# CLOCK_GENERATOR.net
KiCad netlist of a schematic drawn in Altium Designer
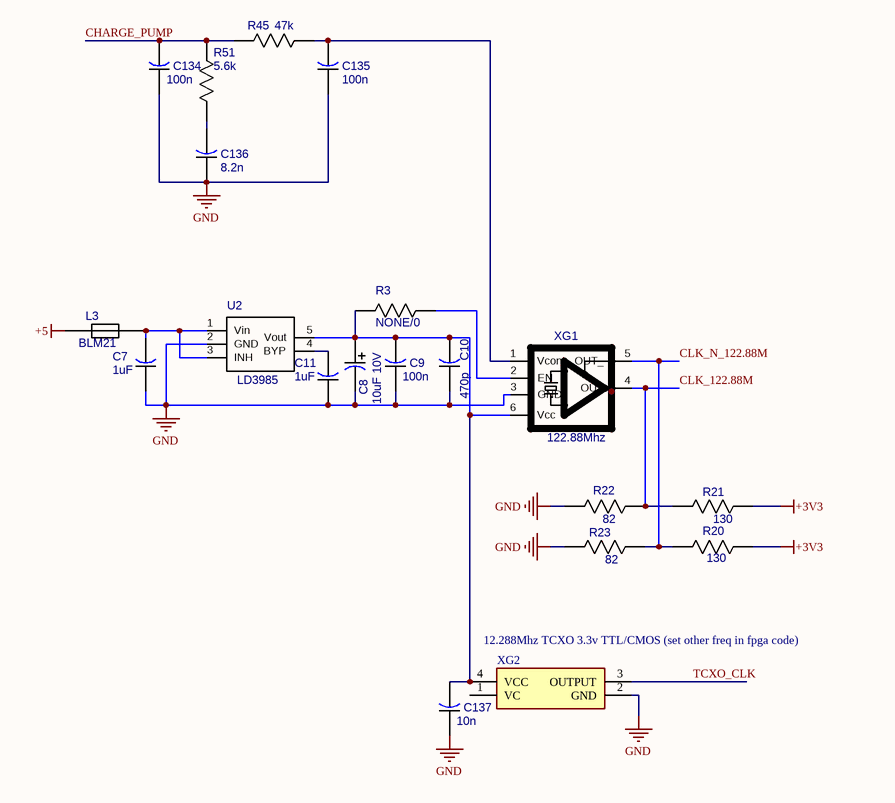
[diagram p0: CLOCK_GENERATOR.SchDoc]

(export (version "E")
  (design (tool "Eeschema 10.0.6"))
  (components
    (comp (ref "C7")
      (value "1uF")
      (footprint "CAP_0805")
      (description "CAP_0805")
      (libsource (lib "*") (part "CAP_0805"))
    )
    (comp (ref "C8")
      (value "10uF 10V")
      (footprint "CAPAE_4.3x4.3h5.4")
      (description "CAPAE_4.3x4.3h5.4")
      (libsource (lib "*") (part "CAPAE_4.3x4.3h5.4"))
    )
    (comp (ref "C9")
      (value "100n")
      (footprint "CAP_0805")
      (description "CAP_0805")
      (libsource (lib "*") (part "CAP_0805"))
    )
    (comp (ref "C10")
      (value "470p")
      (footprint "CAP_0805")
      (description "CAP_0805")
      (libsource (lib "*") (part "CAP_0805"))
    )
    (comp (ref "C11")
      (value "1uF")
      (footprint "CAP_0805")
      (description "CAP_0805")
      (libsource (lib "*") (part "CAP_0805"))
    )
    (comp (ref "C134")
      (value "100n")
      (footprint "CAP_0805")
      (description "CAP_0805")
      (libsource (lib "*") (part "CAP_0805"))
    )
    (comp (ref "C135")
      (value "100n")
      (footprint "CAP_0805")
      (description "CAP_0805")
      (libsource (lib "*") (part "CAP_0805"))
    )
    (comp (ref "C136")
      (value "8.2n")
      (footprint "CAP_0805")
      (description "CAP_0805")
      (libsource (lib "*") (part "CAP_0805"))
    )
    (comp (ref "C137")
      (value "10n")
      (footprint "CAP_0805")
      (description "CAP_0805")
      (libsource (lib "*") (part "CAP_0805"))
    )
    (comp (ref "L3")
      (value "BLM21")
      (footprint "CAP_0805")
      (libsource (lib "MOTHERBOARD_1") (part "IND_FERRITE_BEAD"))
    )
    (comp (ref "R3")
      (value "NONE/0")
      (footprint "RES_0805")
      (description "By used crystal")
      (fields (field (name "Comment") "0/NONE"))
      (libsource (lib "*") (part "RES_0805"))
    )
    (comp (ref "R20")
      (value "130")
      (footprint "RES_0805")
      (description "RES_0805")
      (libsource (lib "*") (part "RES_0805"))
    )
    (comp (ref "R21")
      (value "130")
      (footprint "RES_0805")
      (description "RES_0805")
      (libsource (lib "*") (part "RES_0805"))
    )
    (comp (ref "R22")
      (value "82")
      (footprint "RES_0805")
      (description "RES_0805")
      (libsource (lib "*") (part "RES_0805"))
    )
    (comp (ref "R23")
      (value "82")
      (footprint "RES_0805")
      (description "RES_0805")
      (libsource (lib "*") (part "RES_0805"))
    )
    (comp (ref "R45")
      (value "47k")
      (footprint "RES_0805")
      (description "RES_0805")
      (libsource (lib "*") (part "RES_0805"))
    )
    (comp (ref "R51")
      (value "5.6k")
      (footprint "RES_0805")
      (description "RES_0805")
      (libsource (lib "*") (part "RES_0805"))
    )
    (comp (ref "U2") (value "LD3985") (footprint "LD3985") (libsource (lib "*") (part "LD3985")))
    (comp (ref "XG1")
      (value "122.88Mhz")
      (footprint "NV7050SA")
      (description "NV7050SA\r\nVG-4513CA-122.8800M-GGCT3")
      (libsource (lib "*") (part "NV7050SA"))
    )
    (comp (ref "XG2")
      (value "12.288Mhz TCXO 3.3v TTL/CMOS (set other freq in fpga code)")
      (footprint "SamacSys:581L200X2ITT")
      (description "Crystal or Oscillator")
      (fields
        (field (name "MANUFACTURER_PART_NUMBER") "581L200X2ITT")
        (field (name "MOUSER PART NUMBER") "774-581L200X2ITT")
      )
      (libsource (lib "*") (part "581L200X2ITT"))
    )
  )
  (nets
    (net (code "1") (name "+3V3") (class "Default")
      (node (ref "R20") (pin "1") (pinfunction "1_1") (pintype "passive"))
      (node (ref "R21") (pin "1") (pinfunction "1_1") (pintype "passive"))
    )
    (net (code "2") (name "+5") (class "Default")
      (node (ref "L3") (pin "1") (pinfunction "1_1") (pintype "passive"))
    )
    (net (code "3") (name "/CHARGE_PUMP") (class "Default")
      (node (ref "C134") (pin "2") (pinfunction "2_2") (pintype "passive"))
      (node (ref "R45") (pin "1") (pinfunction "1_1") (pintype "passive"))
      (node (ref "R51") (pin "1") (pinfunction "1_1") (pintype "passive"))
    )
    (net (code "4") (name "/CLK_122.88M") (class "Default")
      (node (ref "R21") (pin "2") (pinfunction "2_2") (pintype "passive"))
      (node (ref "R22") (pin "1") (pinfunction "1_1") (pintype "passive"))
      (node (ref "XG1") (pin "4") (pinfunction "OUT_4") (pintype "passive"))
    )
    (net (code "5") (name "/CLK_N_122.88M") (class "Default")
      (node (ref "R20") (pin "2") (pinfunction "2_2") (pintype "passive"))
      (node (ref "R23") (pin "1") (pinfunction "1_1") (pintype "passive"))
      (node (ref "XG1") (pin "5") (pinfunction "OUT__5") (pintype "passive"))
    )
    (net (code "6") (name "/TCXO_CLK") (class "Default")
      (node (ref "XG2") (pin "3") (pinfunction "OUTPUT_3") (pintype "passive"))
    )
    (net (code "7") (name "GND") (class "Default")
      (node (ref "C10") (pin "1") (pinfunction "1_1") (pintype "passive"))
      (node (ref "C11") (pin "1") (pinfunction "1_1") (pintype "passive"))
      (node (ref "C134") (pin "1") (pinfunction "1_1") (pintype "passive"))
      (node (ref "C135") (pin "1") (pinfunction "1_1") (pintype "passive"))
      (node (ref "C136") (pin "1") (pinfunction "1_1") (pintype "passive"))
      (node (ref "C137") (pin "1") (pinfunction "1_1") (pintype "passive"))
      (node (ref "C7") (pin "1") (pinfunction "1_1") (pintype "passive"))
      (node (ref "C8") (pin "2") (pinfunction "MINUS_2") (pintype "passive"))
      (node (ref "C9") (pin "1") (pinfunction "1_1") (pintype "passive"))
      (node (ref "R22") (pin "2") (pinfunction "2_2") (pintype "passive"))
      (node (ref "R23") (pin "2") (pinfunction "2_2") (pintype "passive"))
      (node (ref "U2") (pin "2") (pinfunction "GND_2") (pintype "passive"))
      (node (ref "XG1") (pin "3") (pinfunction "GND_3") (pintype "passive"))
      (node (ref "XG2") (pin "2") (pinfunction "GND_2") (pintype "passive"))
    )
    (net (code "8") (name "Net-(C8-PLUS)") (class "Default")
      (node (ref "C10") (pin "2") (pinfunction "2_2") (pintype "passive"))
      (node (ref "C137") (pin "2") (pinfunction "2_2") (pintype "passive"))
      (node (ref "C8") (pin "1") (pinfunction "PLUS_1") (pintype "passive"))
      (node (ref "C9") (pin "2") (pinfunction "2_2") (pintype "passive"))
      (node (ref "R3") (pin "1") (pinfunction "1_1") (pintype "passive"))
      (node (ref "U2") (pin "5") (pinfunction "Vout_5") (pintype "passive"))
      (node (ref "XG1") (pin "6") (pinfunction "Vcc_6") (pintype "passive"))
      (node (ref "XG2") (pin "4") (pinfunction "VCC_4") (pintype "passive"))
    )
    (net (code "9") (name "Net-(C136-Pad2)") (class "Default")
      (node (ref "C136") (pin "2") (pinfunction "2_2") (pintype "passive"))
      (node (ref "R51") (pin "2") (pinfunction "2_2") (pintype "passive"))
    )
    (net (code "10") (name "Net-(U2-BYP)") (class "Default")
      (node (ref "C11") (pin "2") (pinfunction "2_2") (pintype "passive"))
      (node (ref "U2") (pin "4") (pinfunction "BYP_4") (pintype "passive"))
    )
    (net (code "11") (name "Net-(U2-INH)") (class "Default")
      (node (ref "C7") (pin "2") (pinfunction "2_2") (pintype "passive"))
      (node (ref "L3") (pin "2") (pinfunction "2_2") (pintype "passive"))
      (node (ref "U2") (pin "1") (pinfunction "Vin_1") (pintype "passive"))
      (node (ref "U2") (pin "3") (pinfunction "INH_3") (pintype "passive"))
    )
    (net (code "12") (name "Net-(XG1-EN)") (class "Default")
      (node (ref "R3") (pin "2") (pinfunction "2_2") (pintype "passive"))
      (node (ref "XG1") (pin "2") (pinfunction "EN_2") (pintype "passive"))
    )
    (net (code "13") (name "Net-(XG1-Vcont)") (class "Default")
      (node (ref "C135") (pin "2") (pinfunction "2_2") (pintype "passive"))
      (node (ref "R45") (pin "2") (pinfunction "2_2") (pintype "passive"))
      (node (ref "XG1") (pin "1") (pinfunction "Vcont_1") (pintype "passive"))
    )
    (net (code "14") (name "unconnected-(XG2-VC-Pad1)") (class "Default")
      (node (ref "XG2") (pin "1") (pinfunction "VC_1") (pintype "passive"))
    )
  )
)
